# ServoShield_v2_2.net
KiCad netlist of a schematic drawn in EAGLE
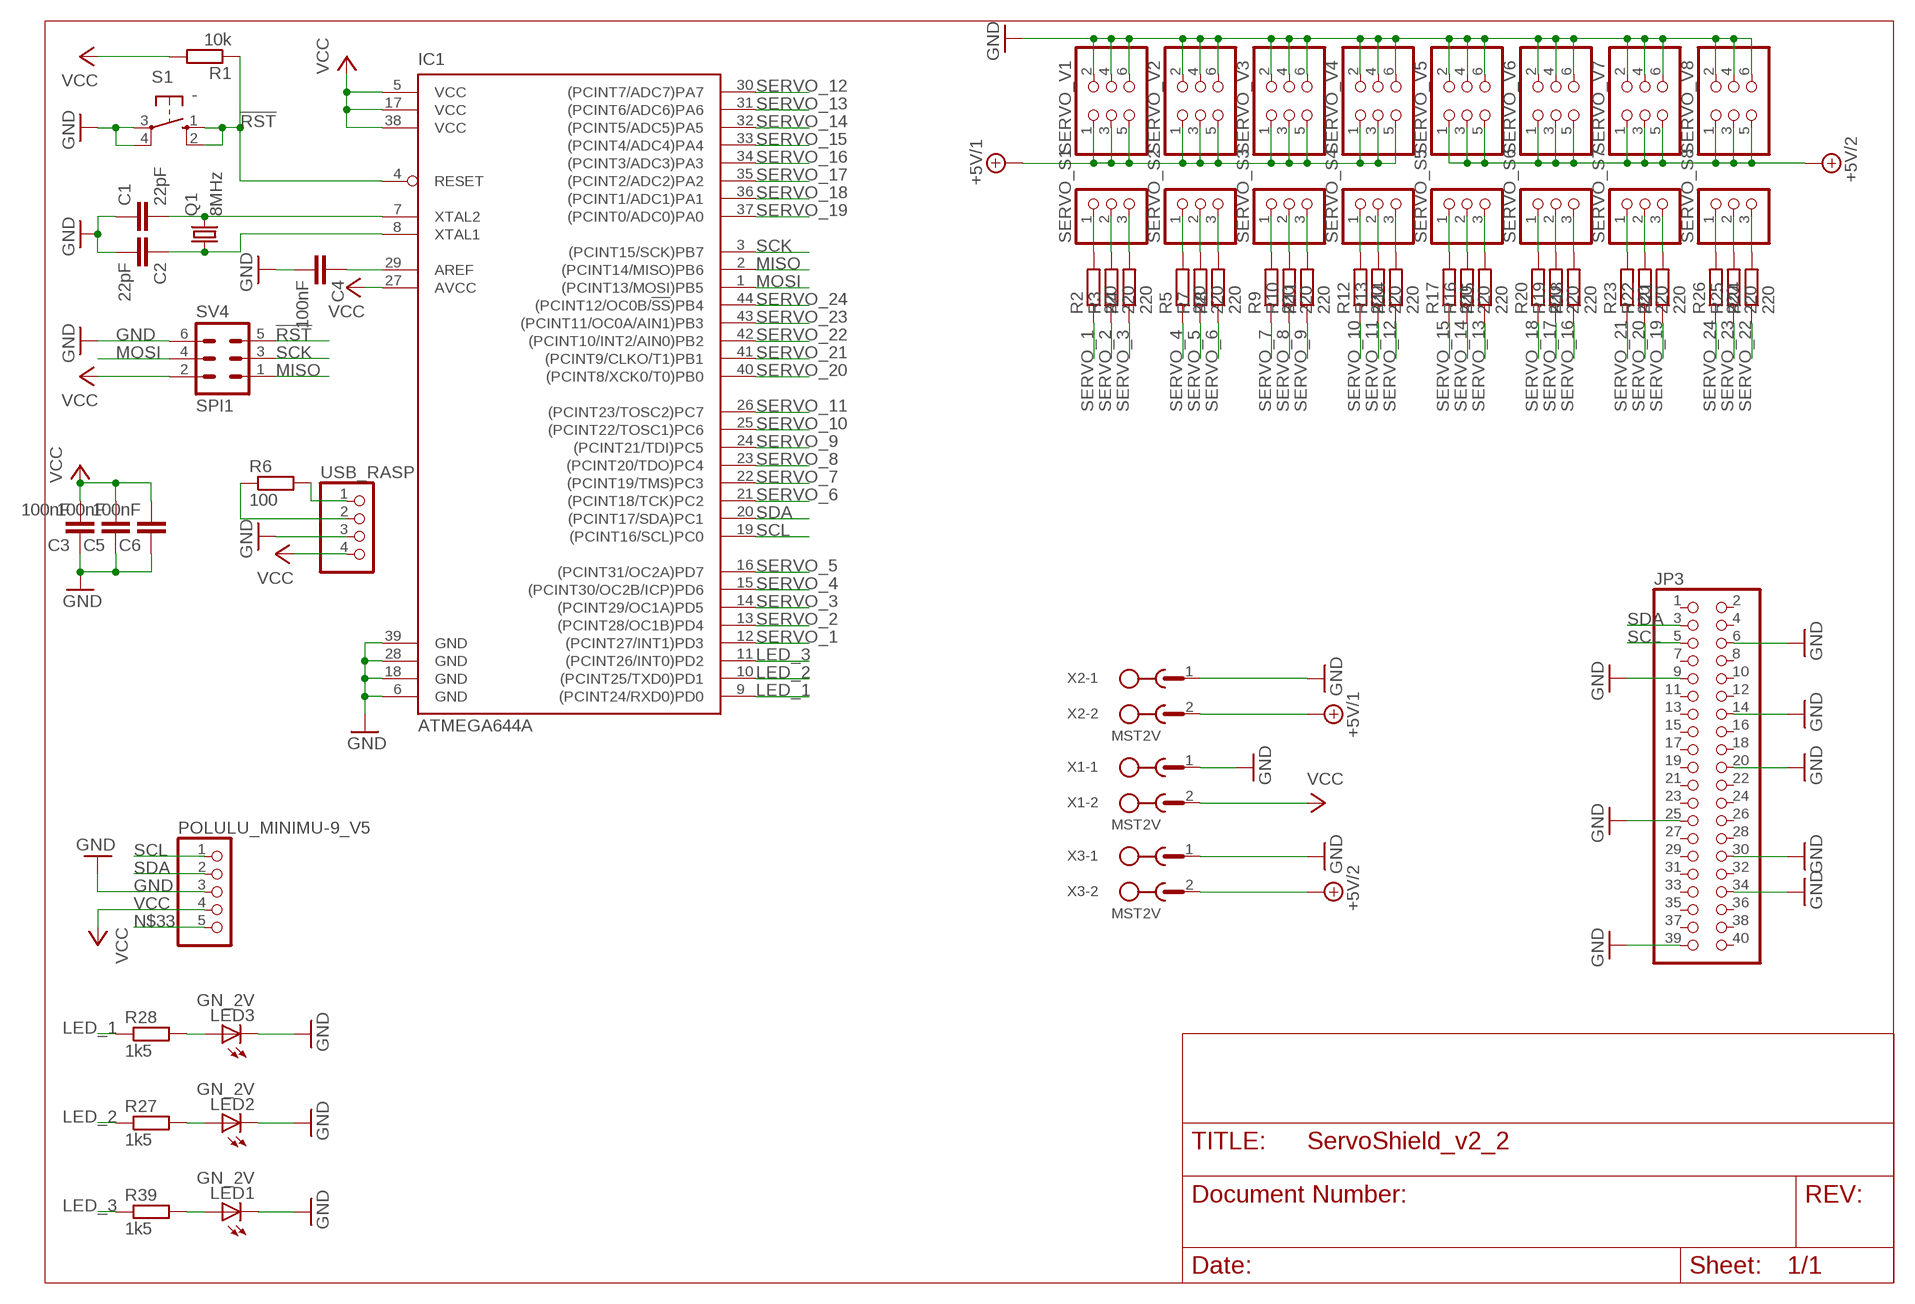
[diagram p0: schematic, sheet 1]

(export (version "E")
  (design (tool "Eeschema 10.0.6"))
  (components
    (comp (ref "C1")
      (value "22pF")
      (footprint "eagle-import:C0805")
      (libsource (lib "eagle-import") (part "C-EUC0805"))
    )
    (comp (ref "C2")
      (value "22pF")
      (footprint "eagle-import:C0805")
      (libsource (lib "eagle-import") (part "C-EUC0805"))
    )
    (comp (ref "C3")
      (value "100nF")
      (footprint "eagle-import:C0805")
      (libsource (lib "eagle-import") (part "resistor_C-EUC0805"))
    )
    (comp (ref "C4")
      (value "100nF")
      (footprint "eagle-import:C0805")
      (libsource (lib "eagle-import") (part "resistor_C-EUC0805"))
    )
    (comp (ref "C5")
      (value "100nF")
      (footprint "eagle-import:C0805")
      (libsource (lib "eagle-import") (part "resistor_C-EUC0805"))
    )
    (comp (ref "C6")
      (value "100nF")
      (footprint "eagle-import:C0805")
      (libsource (lib "eagle-import") (part "resistor_C-EUC0805"))
    )
    (comp (ref "IC1")
      (value "ATMEGA644A")
      (footprint "eagle-import:TQFP44")
      (fields (field (name "MPN") "ATMEGA644PV-10AU"))
      (libsource (lib "eagle-import") (part "ATMEGA644A"))
    )
    (comp (ref "JP3")
      (value "PINHD-2X20")
      (footprint "eagle-import:2X20")
      (libsource (lib "eagle-import") (part "PINHD-2X20"))
    )
    (comp (ref "LED1")
      (value "GN_2V")
      (footprint "eagle-import:LED3MM")
      (libsource (lib "eagle-import") (part "LED3MM"))
    )
    (comp (ref "LED2")
      (value "GN_2V")
      (footprint "eagle-import:LED3MM")
      (libsource (lib "eagle-import") (part "LED3MM"))
    )
    (comp (ref "LED3")
      (value "GN_2V")
      (footprint "eagle-import:LED3MM")
      (libsource (lib "eagle-import") (part "LED3MM"))
    )
    (comp (ref "POLULU_MINIMU-9_V5")
      (value "PINHD-1X5")
      (footprint "eagle-import:1X05")
      (libsource (lib "eagle-import") (part "PINHD-1X5"))
    )
    (comp (ref "Q1")
      (value "8MHz")
      (footprint "eagle-import:CTS406")
      (libsource (lib "eagle-import") (part "CRYSTALCTS406"))
    )
    (comp (ref "R1")
      (value "10k")
      (footprint "eagle-import:R0805")
      (libsource (lib "eagle-import") (part "resistor_R-EU_R0805"))
    )
    (comp (ref "R2")
      (value "220")
      (footprint "eagle-import:R0805")
      (libsource (lib "eagle-import") (part "resistor_R-EU_R0805"))
    )
    (comp (ref "R3")
      (value "220")
      (footprint "eagle-import:R0805")
      (libsource (lib "eagle-import") (part "resistor_R-EU_R0805"))
    )
    (comp (ref "R4")
      (value "220")
      (footprint "eagle-import:R0805")
      (libsource (lib "eagle-import") (part "resistor_R-EU_R0805"))
    )
    (comp (ref "R5")
      (value "220")
      (footprint "eagle-import:R0805")
      (libsource (lib "eagle-import") (part "resistor_R-EU_R0805"))
    )
    (comp (ref "R6")
      (value "100")
      (footprint "eagle-import:R0805")
      (libsource (lib "eagle-import") (part "R-EU_R0805"))
    )
    (comp (ref "R7")
      (value "220")
      (footprint "eagle-import:R0805")
      (libsource (lib "eagle-import") (part "resistor_R-EU_R0805"))
    )
    (comp (ref "R8")
      (value "220")
      (footprint "eagle-import:R0805")
      (libsource (lib "eagle-import") (part "resistor_R-EU_R0805"))
    )
    (comp (ref "R9")
      (value "220")
      (footprint "eagle-import:R0805")
      (libsource (lib "eagle-import") (part "resistor_R-EU_R0805"))
    )
    (comp (ref "R10")
      (value "220")
      (footprint "eagle-import:R0805")
      (libsource (lib "eagle-import") (part "resistor_R-EU_R0805"))
    )
    (comp (ref "R11")
      (value "220")
      (footprint "eagle-import:R0805")
      (libsource (lib "eagle-import") (part "resistor_R-EU_R0805"))
    )
    (comp (ref "R12")
      (value "220")
      (footprint "eagle-import:R0805")
      (libsource (lib "eagle-import") (part "resistor_R-EU_R0805"))
    )
    (comp (ref "R13")
      (value "220")
      (footprint "eagle-import:R0805")
      (libsource (lib "eagle-import") (part "resistor_R-EU_R0805"))
    )
    (comp (ref "R14")
      (value "220")
      (footprint "eagle-import:R0805")
      (libsource (lib "eagle-import") (part "resistor_R-EU_R0805"))
    )
    (comp (ref "R15")
      (value "220")
      (footprint "eagle-import:R0805")
      (libsource (lib "eagle-import") (part "resistor_R-EU_R0805"))
    )
    (comp (ref "R16")
      (value "220")
      (footprint "eagle-import:R0805")
      (libsource (lib "eagle-import") (part "resistor_R-EU_R0805"))
    )
    (comp (ref "R17")
      (value "220")
      (footprint "eagle-import:R0805")
      (libsource (lib "eagle-import") (part "resistor_R-EU_R0805"))
    )
    (comp (ref "R18")
      (value "220")
      (footprint "eagle-import:R0805")
      (libsource (lib "eagle-import") (part "resistor_R-EU_R0805"))
    )
    (comp (ref "R19")
      (value "220")
      (footprint "eagle-import:R0805")
      (libsource (lib "eagle-import") (part "resistor_R-EU_R0805"))
    )
    (comp (ref "R20")
      (value "220")
      (footprint "eagle-import:R0805")
      (libsource (lib "eagle-import") (part "resistor_R-EU_R0805"))
    )
    (comp (ref "R21")
      (value "220")
      (footprint "eagle-import:R0805")
      (libsource (lib "eagle-import") (part "resistor_R-EU_R0805"))
    )
    (comp (ref "R22")
      (value "220")
      (footprint "eagle-import:R0805")
      (libsource (lib "eagle-import") (part "resistor_R-EU_R0805"))
    )
    (comp (ref "R23")
      (value "220")
      (footprint "eagle-import:R0805")
      (libsource (lib "eagle-import") (part "resistor_R-EU_R0805"))
    )
    (comp (ref "R24")
      (value "220")
      (footprint "eagle-import:R0805")
      (libsource (lib "eagle-import") (part "resistor_R-EU_R0805"))
    )
    (comp (ref "R25")
      (value "220")
      (footprint "eagle-import:R0805")
      (libsource (lib "eagle-import") (part "resistor_R-EU_R0805"))
    )
    (comp (ref "R26")
      (value "220")
      (footprint "eagle-import:R0805")
      (libsource (lib "eagle-import") (part "resistor_R-EU_R0805"))
    )
    (comp (ref "R27")
      (value "1k5")
      (footprint "eagle-import:R0805")
      (libsource (lib "eagle-import") (part "R-EU_R0805"))
    )
    (comp (ref "R28")
      (value "1k5")
      (footprint "eagle-import:R0805")
      (libsource (lib "eagle-import") (part "R-EU_R0805"))
    )
    (comp (ref "R39")
      (value "1k5")
      (footprint "eagle-import:R0805")
      (libsource (lib "eagle-import") (part "R-EU_R0805"))
    )
    (comp (ref "S1")
      (value "-")
      (footprint "eagle-import:B3F-10XX")
      (fields (field (name "MPN") "B3F-1000"))
      (libsource (lib "eagle-import") (part "10-XX"))
    )
    (comp (ref "SERVO_S1")
      (value "PINHD-1X3")
      (footprint "eagle-import:1X03")
      (libsource (lib "eagle-import") (part "PINHD-1X3"))
    )
    (comp (ref "SERVO_S2")
      (value "PINHD-1X3")
      (footprint "eagle-import:1X03")
      (libsource (lib "eagle-import") (part "PINHD-1X3"))
    )
    (comp (ref "SERVO_S3")
      (value "PINHD-1X3")
      (footprint "eagle-import:1X03")
      (libsource (lib "eagle-import") (part "PINHD-1X3"))
    )
    (comp (ref "SERVO_S4")
      (value "PINHD-1X3")
      (footprint "eagle-import:1X03")
      (libsource (lib "eagle-import") (part "PINHD-1X3"))
    )
    (comp (ref "SERVO_S5")
      (value "PINHD-1X3")
      (footprint "eagle-import:1X03")
      (libsource (lib "eagle-import") (part "PINHD-1X3"))
    )
    (comp (ref "SERVO_S6")
      (value "PINHD-1X3")
      (footprint "eagle-import:1X03")
      (libsource (lib "eagle-import") (part "PINHD-1X3"))
    )
    (comp (ref "SERVO_S7")
      (value "PINHD-1X3")
      (footprint "eagle-import:1X03")
      (libsource (lib "eagle-import") (part "PINHD-1X3"))
    )
    (comp (ref "SERVO_S8")
      (value "PINHD-1X3")
      (footprint "eagle-import:1X03")
      (libsource (lib "eagle-import") (part "PINHD-1X3"))
    )
    (comp (ref "SERVO_V1")
      (value "PINHD-2X3")
      (footprint "eagle-import:2X03")
      (libsource (lib "eagle-import") (part "PINHD-2X3"))
    )
    (comp (ref "SERVO_V2")
      (value "PINHD-2X3")
      (footprint "eagle-import:2X03")
      (libsource (lib "eagle-import") (part "PINHD-2X3"))
    )
    (comp (ref "SERVO_V3")
      (value "PINHD-2X3")
      (footprint "eagle-import:2X03")
      (libsource (lib "eagle-import") (part "PINHD-2X3"))
    )
    (comp (ref "SERVO_V4")
      (value "PINHD-2X3")
      (footprint "eagle-import:2X03")
      (libsource (lib "eagle-import") (part "PINHD-2X3"))
    )
    (comp (ref "SERVO_V5")
      (value "PINHD-2X3")
      (footprint "eagle-import:2X03")
      (libsource (lib "eagle-import") (part "PINHD-2X3"))
    )
    (comp (ref "SERVO_V6")
      (value "PINHD-2X3")
      (footprint "eagle-import:2X03")
      (libsource (lib "eagle-import") (part "PINHD-2X3"))
    )
    (comp (ref "SERVO_V7")
      (value "PINHD-2X3")
      (footprint "eagle-import:2X03")
      (libsource (lib "eagle-import") (part "PINHD-2X3"))
    )
    (comp (ref "SERVO_V8")
      (value "PINHD-2X3")
      (footprint "eagle-import:2X03")
      (libsource (lib "eagle-import") (part "PINHD-2X3"))
    )
    (comp (ref "SV4")
      (value "SPI1")
      (footprint "eagle-import:ML6")
      (libsource (lib "eagle-import") (part "ML6"))
    )
    (comp (ref "USB_RASP")
      (value "PINHD-1X4")
      (footprint "eagle-import:1X04")
      (libsource (lib "eagle-import") (part "PINHD-1X4"))
    )
    (comp (ref "X1")
      (value "MST2V")
      (footprint "eagle-import:MSTBV2")
      (libsource (lib "eagle-import") (part "MST2V"))
    )
    (comp (ref "X2")
      (value "MST2V")
      (footprint "eagle-import:MSTBV2")
      (libsource (lib "eagle-import") (part "MST2V"))
    )
    (comp (ref "X3")
      (value "MST2V")
      (footprint "eagle-import:MSTBV2")
      (libsource (lib "eagle-import") (part "MST2V"))
    )
  )
  (nets
    (net (code "1") (name "+5V{slash}1") (class "Default")
      (node (ref "SERVO_V1") (pin "1") (pinfunction "1_1") (pintype "passive"))
      (node (ref "SERVO_V1") (pin "3") (pinfunction "3_3") (pintype "passive"))
      (node (ref "SERVO_V1") (pin "5") (pinfunction "5_5") (pintype "passive"))
      (node (ref "SERVO_V2") (pin "1") (pinfunction "1_1") (pintype "passive"))
      (node (ref "SERVO_V2") (pin "3") (pinfunction "3_3") (pintype "passive"))
      (node (ref "SERVO_V2") (pin "5") (pinfunction "5_5") (pintype "passive"))
      (node (ref "SERVO_V3") (pin "1") (pinfunction "1_1") (pintype "passive"))
      (node (ref "SERVO_V3") (pin "3") (pinfunction "3_3") (pintype "passive"))
      (node (ref "SERVO_V3") (pin "5") (pinfunction "5_5") (pintype "passive"))
      (node (ref "SERVO_V4") (pin "1") (pinfunction "1_1") (pintype "passive"))
      (node (ref "SERVO_V4") (pin "3") (pinfunction "3_3") (pintype "passive"))
      (node (ref "SERVO_V4") (pin "5") (pinfunction "5_5") (pintype "passive"))
      (node (ref "X2") (pin "2") (pinfunction "1_2") (pintype "passive"))
    )
    (net (code "2") (name "+5V{slash}2") (class "Default")
      (node (ref "SERVO_V5") (pin "1") (pinfunction "1_1") (pintype "passive"))
      (node (ref "SERVO_V5") (pin "3") (pinfunction "3_3") (pintype "passive"))
      (node (ref "SERVO_V5") (pin "5") (pinfunction "5_5") (pintype "passive"))
      (node (ref "SERVO_V6") (pin "1") (pinfunction "1_1") (pintype "passive"))
      (node (ref "SERVO_V6") (pin "3") (pinfunction "3_3") (pintype "passive"))
      (node (ref "SERVO_V6") (pin "5") (pinfunction "5_5") (pintype "passive"))
      (node (ref "SERVO_V7") (pin "1") (pinfunction "1_1") (pintype "passive"))
      (node (ref "SERVO_V7") (pin "3") (pinfunction "3_3") (pintype "passive"))
      (node (ref "SERVO_V7") (pin "5") (pinfunction "5_5") (pintype "passive"))
      (node (ref "SERVO_V8") (pin "1") (pinfunction "1_1") (pintype "passive"))
      (node (ref "SERVO_V8") (pin "3") (pinfunction "3_3") (pintype "passive"))
      (node (ref "SERVO_V8") (pin "5") (pinfunction "5_5") (pintype "passive"))
      (node (ref "X3") (pin "2") (pinfunction "1_2") (pintype "passive"))
    )
    (net (code "3") (name "/LED_1") (class "Default")
      (node (ref "IC1") (pin "9") (pinfunction "(PCINT24/RXD0)PD0_9") (pintype "bidirectional"))
      (node (ref "R28") (pin "1") (pinfunction "1_1") (pintype "passive"))
    )
    (net (code "4") (name "/LED_2") (class "Default")
      (node (ref "IC1") (pin "10") (pinfunction "(PCINT25/TXD0)PD1_10") (pintype "bidirectional"))
      (node (ref "R27") (pin "1") (pinfunction "1_1") (pintype "passive"))
    )
    (net (code "5") (name "/LED_3") (class "Default")
      (node (ref "IC1") (pin "11") (pinfunction "(PCINT26/INT0)PD2_11") (pintype "bidirectional"))
      (node (ref "R39") (pin "1") (pinfunction "1_1") (pintype "passive"))
    )
    (net (code "6") (name "/MISO") (class "Default")
      (node (ref "IC1") (pin "2") (pinfunction "(PCINT14/MISO)PB6_2") (pintype "bidirectional"))
      (node (ref "SV4") (pin "1") (pinfunction "1_1") (pintype "passive"))
    )
    (net (code "7") (name "/MOSI") (class "Default")
      (node (ref "IC1") (pin "1") (pinfunction "(PCINT13/MOSI)PB5_1") (pintype "bidirectional"))
      (node (ref "SV4") (pin "4") (pinfunction "4_4") (pintype "passive"))
    )
    (net (code "8") (name "/N$33") (class "Default")
      (node (ref "POLULU_MINIMU-9_V5") (pin "5") (pinfunction "5_5") (pintype "passive"))
    )
    (net (code "9") (name "/SCK") (class "Default")
      (node (ref "IC1") (pin "3") (pinfunction "(PCINT15/SCK)PB7_3") (pintype "bidirectional"))
      (node (ref "SV4") (pin "3") (pinfunction "3_3") (pintype "passive"))
    )
    (net (code "10") (name "/SCL") (class "Default")
      (node (ref "IC1") (pin "19") (pinfunction "(PCINT16/SCL)PC0_19") (pintype "output"))
      (node (ref "JP3") (pin "5") (pinfunction "5_5") (pintype "passive"))
      (node (ref "POLULU_MINIMU-9_V5") (pin "1") (pinfunction "1_1") (pintype "passive"))
    )
    (net (code "11") (name "/SDA") (class "Default")
      (node (ref "IC1") (pin "20") (pinfunction "(PCINT17/SDA)PC1_20") (pintype "output"))
      (node (ref "JP3") (pin "3") (pinfunction "3_3") (pintype "passive"))
      (node (ref "POLULU_MINIMU-9_V5") (pin "2") (pinfunction "2_2") (pintype "passive"))
    )
    (net (code "12") (name "/SERVO_1") (class "Default")
      (node (ref "IC1") (pin "12") (pinfunction "(PCINT27/INT1)PD3_12") (pintype "bidirectional"))
      (node (ref "R2") (pin "1") (pinfunction "1_1") (pintype "passive"))
    )
    (net (code "13") (name "/SERVO_2") (class "Default")
      (node (ref "IC1") (pin "13") (pinfunction "(PCINT28/OC1B)PD4_13") (pintype "bidirectional"))
      (node (ref "R3") (pin "1") (pinfunction "1_1") (pintype "passive"))
    )
    (net (code "14") (name "/SERVO_3") (class "Default")
      (node (ref "IC1") (pin "14") (pinfunction "(PCINT29/OC1A)PD5_14") (pintype "bidirectional"))
      (node (ref "R4") (pin "1") (pinfunction "1_1") (pintype "passive"))
    )
    (net (code "15") (name "/SERVO_4") (class "Default")
      (node (ref "IC1") (pin "15") (pinfunction "(PCINT30/OC2B/ICP)PD6_15") (pintype "bidirectional"))
      (node (ref "R5") (pin "1") (pinfunction "1_1") (pintype "passive"))
    )
    (net (code "16") (name "/SERVO_5") (class "Default")
      (node (ref "IC1") (pin "16") (pinfunction "(PCINT31/OC2A)PD7_16") (pintype "bidirectional"))
      (node (ref "R7") (pin "1") (pinfunction "1_1") (pintype "passive"))
    )
    (net (code "17") (name "/SERVO_6") (class "Default")
      (node (ref "IC1") (pin "21") (pinfunction "(PCINT18/TCK)PC2_21") (pintype "output"))
      (node (ref "R8") (pin "1") (pinfunction "1_1") (pintype "passive"))
    )
    (net (code "18") (name "/SERVO_7") (class "Default")
      (node (ref "IC1") (pin "22") (pinfunction "(PCINT19/TMS)PC3_22") (pintype "output"))
      (node (ref "R9") (pin "1") (pinfunction "1_1") (pintype "passive"))
    )
    (net (code "19") (name "/SERVO_8") (class "Default")
      (node (ref "IC1") (pin "23") (pinfunction "(PCINT20/TDO)PC4_23") (pintype "output"))
      (node (ref "R10") (pin "1") (pinfunction "1_1") (pintype "passive"))
    )
    (net (code "20") (name "/SERVO_9") (class "Default")
      (node (ref "IC1") (pin "24") (pinfunction "(PCINT21/TDI)PC5_24") (pintype "output"))
      (node (ref "R11") (pin "1") (pinfunction "1_1") (pintype "passive"))
    )
    (net (code "21") (name "/SERVO_10") (class "Default")
      (node (ref "IC1") (pin "25") (pinfunction "(PCINT22/TOSC1)PC6_25") (pintype "output"))
      (node (ref "R12") (pin "1") (pinfunction "1_1") (pintype "passive"))
    )
    (net (code "22") (name "/SERVO_11") (class "Default")
      (node (ref "IC1") (pin "26") (pinfunction "(PCINT23/TOSC2)PC7_26") (pintype "output"))
      (node (ref "R13") (pin "1") (pinfunction "1_1") (pintype "passive"))
    )
    (net (code "23") (name "/SERVO_12") (class "Default")
      (node (ref "IC1") (pin "30") (pinfunction "(PCINT7/ADC7)PA7_30") (pintype "bidirectional"))
      (node (ref "R14") (pin "1") (pinfunction "1_1") (pintype "passive"))
    )
    (net (code "24") (name "/SERVO_13") (class "Default")
      (node (ref "IC1") (pin "31") (pinfunction "(PCINT6/ADC6)PA6_31") (pintype "bidirectional"))
      (node (ref "R15") (pin "1") (pinfunction "1_1") (pintype "passive"))
    )
    (net (code "25") (name "/SERVO_14") (class "Default")
      (node (ref "IC1") (pin "32") (pinfunction "(PCINT5/ADC5)PA5_32") (pintype "bidirectional"))
      (node (ref "R16") (pin "1") (pinfunction "1_1") (pintype "passive"))
    )
    (net (code "26") (name "/SERVO_15") (class "Default")
      (node (ref "IC1") (pin "33") (pinfunction "(PCINT4/ADC4)PA4_33") (pintype "bidirectional"))
      (node (ref "R17") (pin "1") (pinfunction "1_1") (pintype "passive"))
    )
    (net (code "27") (name "/SERVO_16") (class "Default")
      (node (ref "IC1") (pin "34") (pinfunction "(PCINT3/ADC3)PA3_34") (pintype "bidirectional"))
      (node (ref "R18") (pin "1") (pinfunction "1_1") (pintype "passive"))
    )
    (net (code "28") (name "/SERVO_17") (class "Default")
      (node (ref "IC1") (pin "35") (pinfunction "(PCINT2/ADC2)PA2_35") (pintype "bidirectional"))
      (node (ref "R19") (pin "1") (pinfunction "1_1") (pintype "passive"))
    )
    (net (code "29") (name "/SERVO_18") (class "Default")
      (node (ref "IC1") (pin "36") (pinfunction "(PCINT1/ADC1)PA1_36") (pintype "bidirectional"))
      (node (ref "R20") (pin "1") (pinfunction "1_1") (pintype "passive"))
    )
    (net (code "30") (name "/SERVO_19") (class "Default")
      (node (ref "IC1") (pin "37") (pinfunction "(PCINT0/ADC0)PA0_37") (pintype "bidirectional"))
      (node (ref "R21") (pin "1") (pinfunction "1_1") (pintype "passive"))
    )
    (net (code "31") (name "/SERVO_20") (class "Default")
      (node (ref "IC1") (pin "40") (pinfunction "(PCINT8/XCK0/T0)PB0_40") (pintype "bidirectional"))
      (node (ref "R22") (pin "1") (pinfunction "1_1") (pintype "passive"))
    )
    (net (code "32") (name "/SERVO_21") (class "Default")
      (node (ref "IC1") (pin "41") (pinfunction "(PCINT9/CLKO/T1)PB1_41") (pintype "bidirectional"))
      (node (ref "R23") (pin "1") (pinfunction "1_1") (pintype "passive"))
    )
    (net (code "33") (name "/SERVO_22") (class "Default")
      (node (ref "IC1") (pin "42") (pinfunction "(PCINT10/INT2/AIN0)PB2_42") (pintype "bidirectional"))
      (node (ref "R24") (pin "1") (pinfunction "1_1") (pintype "passive"))
    )
    (net (code "34") (name "/SERVO_23") (class "Default")
      (node (ref "IC1") (pin "43") (pinfunction "(PCINT11/OC0A/AIN1)PB3_43") (pintype "bidirectional"))
      (node (ref "R25") (pin "1") (pinfunction "1_1") (pintype "passive"))
    )
    (net (code "35") (name "/SERVO_24") (class "Default")
      (node (ref "IC1") (pin "44") (pinfunction "(PCINT12/OC0B/~{SS})PB4_44") (pintype "bidirectional"))
      (node (ref "R26") (pin "1") (pinfunction "1_1") (pintype "passive"))
    )
    (net (code "36") (name "/~{RST}") (class "Default")
      (node (ref "IC1") (pin "4") (pinfunction "RESET_4") (pintype "input"))
      (node (ref "R1") (pin "1") (pinfunction "1_1") (pintype "passive"))
      (node (ref "S1") (pin "1") (pinfunction "S_1") (pintype "passive"))
      (node (ref "S1") (pin "2") (pinfunction "S1_2") (pintype "passive"))
      (node (ref "SV4") (pin "5") (pinfunction "5_5") (pintype "passive"))
    )
    (net (code "37") (name "GND") (class "Default")
      (node (ref "C1") (pin "1") (pinfunction "1_1") (pintype "passive"))
      (node (ref "C2") (pin "2") (pinfunction "2_2") (pintype "passive"))
      (node (ref "C3") (pin "1") (pinfunction "1_1") (pintype "passive"))
      (node (ref "C4") (pin "2") (pinfunction "2_2") (pintype "passive"))
      (node (ref "C5") (pin "1") (pinfunction "1_1") (pintype "passive"))
      (node (ref "C6") (pin "1") (pinfunction "1_1") (pintype "passive"))
      (node (ref "IC1") (pin "18") (pinfunction "GND_18") (pintype "power_in"))
      (node (ref "IC1") (pin "28") (pinfunction "GND_28") (pintype "power_in"))
      (node (ref "IC1") (pin "39") (pinfunction "GND_39") (pintype "power_in"))
      (node (ref "IC1") (pin "6") (pinfunction "GND_6") (pintype "power_in"))
      (node (ref "JP3") (pin "14") (pinfunction "14_14") (pintype "passive"))
      (node (ref "JP3") (pin "20") (pinfunction "20_20") (pintype "passive"))
      (node (ref "JP3") (pin "25") (pinfunction "25_25") (pintype "passive"))
      (node (ref "JP3") (pin "30") (pinfunction "30_30") (pintype "passive"))
      (node (ref "JP3") (pin "34") (pinfunction "34_34") (pintype "passive"))
      (node (ref "JP3") (pin "39") (pinfunction "39_39") (pintype "passive"))
      (node (ref "JP3") (pin "6") (pinfunction "6_6") (pintype "passive"))
      (node (ref "JP3") (pin "9") (pinfunction "9_9") (pintype "passive"))
      (node (ref "LED1") (pin "K") (pinfunction "C_K") (pintype "passive"))
      (node (ref "LED2") (pin "K") (pinfunction "C_K") (pintype "passive"))
      (node (ref "LED3") (pin "K") (pinfunction "C_K") (pintype "passive"))
      (node (ref "POLULU_MINIMU-9_V5") (pin "3") (pinfunction "3_3") (pintype "passive"))
      (node (ref "S1") (pin "3") (pinfunction "P_3") (pintype "passive"))
      (node (ref "S1") (pin "4") (pinfunction "P1_4") (pintype "passive"))
      (node (ref "SERVO_V1") (pin "2") (pinfunction "2_2") (pintype "passive"))
      (node (ref "SERVO_V1") (pin "4") (pinfunction "4_4") (pintype "passive"))
      (node (ref "SERVO_V1") (pin "6") (pinfunction "6_6") (pintype "passive"))
      (node (ref "SERVO_V2") (pin "2") (pinfunction "2_2") (pintype "passive"))
      (node (ref "SERVO_V2") (pin "4") (pinfunction "4_4") (pintype "passive"))
      (node (ref "SERVO_V2") (pin "6") (pinfunction "6_6") (pintype "passive"))
      (node (ref "SERVO_V3") (pin "2") (pinfunction "2_2") (pintype "passive"))
      (node (ref "SERVO_V3") (pin "4") (pinfunction "4_4") (pintype "passive"))
      (node (ref "SERVO_V3") (pin "6") (pinfunction "6_6") (pintype "passive"))
      (node (ref "SERVO_V4") (pin "2") (pinfunction "2_2") (pintype "passive"))
      (node (ref "SERVO_V4") (pin "4") (pinfunction "4_4") (pintype "passive"))
      (node (ref "SERVO_V4") (pin "6") (pinfunction "6_6") (pintype "passive"))
      (node (ref "SERVO_V5") (pin "2") (pinfunction "2_2") (pintype "passive"))
      (node (ref "SERVO_V5") (pin "4") (pinfunction "4_4") (pintype "passive"))
      (node (ref "SERVO_V5") (pin "6") (pinfunction "6_6") (pintype "passive"))
      (node (ref "SERVO_V6") (pin "2") (pinfunction "2_2") (pintype "passive"))
      (node (ref "SERVO_V6") (pin "4") (pinfunction "4_4") (pintype "passive"))
      (node (ref "SERVO_V6") (pin "6") (pinfunction "6_6") (pintype "passive"))
      (node (ref "SERVO_V7") (pin "2") (pinfunction "2_2") (pintype "passive"))
      (node (ref "SERVO_V7") (pin "4") (pinfunction "4_4") (pintype "passive"))
      (node (ref "SERVO_V7") (pin "6") (pinfunction "6_6") (pintype "passive"))
      (node (ref "SERVO_V8") (pin "2") (pinfunction "2_2") (pintype "passive"))
      (node (ref "SERVO_V8") (pin "4") (pinfunction "4_4") (pintype "passive"))
      (node (ref "SERVO_V8") (pin "6") (pinfunction "6_6") (pintype "passive"))
      (node (ref "SV4") (pin "6") (pinfunction "6_6") (pintype "passive"))
      (node (ref "USB_RASP") (pin "3") (pinfunction "3_3") (pintype "passive"))
      (node (ref "X1") (pin "1") (pinfunction "1_1") (pintype "passive"))
      (node (ref "X2") (pin "1") (pinfunction "1_1") (pintype "passive"))
      (node (ref "X3") (pin "1") (pinfunction "1_1") (pintype "passive"))
    )
    (net (code "38") (name "Net-(IC1-AREF)") (class "Default")
      (node (ref "C4") (pin "1") (pinfunction "1_1") (pintype "passive"))
      (node (ref "IC1") (pin "29") (pinfunction "AREF_29") (pintype "passive"))
    )
    (net (code "39") (name "Net-(IC1-XTAL1)") (class "Default")
      (node (ref "C2") (pin "1") (pinfunction "1_1") (pintype "passive"))
      (node (ref "IC1") (pin "8") (pinfunction "XTAL1_8") (pintype "bidirectional"))
      (node (ref "Q1") (pin "1") (pinfunction "1_1") (pintype "passive"))
    )
    (net (code "40") (name "Net-(IC1-XTAL2)") (class "Default")
      (node (ref "C1") (pin "2") (pinfunction "2_2") (pintype "passive"))
      (node (ref "IC1") (pin "7") (pinfunction "XTAL2_7") (pintype "bidirectional"))
      (node (ref "Q1") (pin "3") (pinfunction "2_3") (pintype "passive"))
    )
    (net (code "41") (name "Net-(LED1-PadA)") (class "Default")
      (node (ref "LED1") (pin "A") (pinfunction "A_A") (pintype "passive"))
      (node (ref "R39") (pin "2") (pinfunction "2_2") (pintype "passive"))
    )
    (net (code "42") (name "Net-(LED2-PadA)") (class "Default")
      (node (ref "LED2") (pin "A") (pinfunction "A_A") (pintype "passive"))
      (node (ref "R27") (pin "2") (pinfunction "2_2") (pintype "passive"))
    )
    (net (code "43") (name "Net-(LED3-PadA)") (class "Default")
      (node (ref "LED3") (pin "A") (pinfunction "A_A") (pintype "passive"))
      (node (ref "R28") (pin "2") (pinfunction "2_2") (pintype "passive"))
    )
    (net (code "44") (name "Net-(R2-Pad2)") (class "Default")
      (node (ref "R2") (pin "2") (pinfunction "2_2") (pintype "passive"))
      (node (ref "SERVO_S1") (pin "1") (pinfunction "1_1") (pintype "passive"))
    )
    (net (code "45") (name "Net-(R3-Pad2)") (class "Default")
      (node (ref "R3") (pin "2") (pinfunction "2_2") (pintype "passive"))
      (node (ref "SERVO_S1") (pin "2") (pinfunction "2_2") (pintype "passive"))
    )
    (net (code "46") (name "Net-(R4-Pad2)") (class "Default")
      (node (ref "R4") (pin "2") (pinfunction "2_2") (pintype "passive"))
      (node (ref "SERVO_S1") (pin "3") (pinfunction "3_3") (pintype "passive"))
    )
    (net (code "47") (name "Net-(R5-Pad2)") (class "Default")
      (node (ref "R5") (pin "2") (pinfunction "2_2") (pintype "passive"))
      (node (ref "SERVO_S2") (pin "1") (pinfunction "1_1") (pintype "passive"))
    )
    (net (code "48") (name "Net-(R6-Pad1)") (class "Default")
      (node (ref "R6") (pin "1") (pinfunction "1_1") (pintype "passive"))
      (node (ref "USB_RASP") (pin "2") (pinfunction "2_2") (pintype "passive"))
    )
    (net (code "49") (name "Net-(R6-Pad2)") (class "Default")
      (node (ref "R6") (pin "2") (pinfunction "2_2") (pintype "passive"))
      (node (ref "USB_RASP") (pin "1") (pinfunction "1_1") (pintype "passive"))
    )
    (net (code "50") (name "Net-(R7-Pad2)") (class "Default")
      (node (ref "R7") (pin "2") (pinfunction "2_2") (pintype "passive"))
      (node (ref "SERVO_S2") (pin "2") (pinfunction "2_2") (pintype "passive"))
    )
    (net (code "51") (name "Net-(R8-Pad2)") (class "Default")
      (node (ref "R8") (pin "2") (pinfunction "2_2") (pintype "passive"))
      (node (ref "SERVO_S2") (pin "3") (pinfunction "3_3") (pintype "passive"))
    )
    (net (code "52") (name "Net-(R9-Pad2)") (class "Default")
      (node (ref "R9") (pin "2") (pinfunction "2_2") (pintype "passive"))
      (node (ref "SERVO_S3") (pin "1") (pinfunction "1_1") (pintype "passive"))
    )
    (net (code "53") (name "Net-(R10-Pad2)") (class "Default")
      (node (ref "R10") (pin "2") (pinfunction "2_2") (pintype "passive"))
      (node (ref "SERVO_S3") (pin "2") (pinfunction "2_2") (pintype "passive"))
    )
    (net (code "54") (name "Net-(R11-Pad2)") (class "Default")
      (node (ref "R11") (pin "2") (pinfunction "2_2") (pintype "passive"))
      (node (ref "SERVO_S3") (pin "3") (pinfunction "3_3") (pintype "passive"))
    )
    (net (code "55") (name "Net-(R12-Pad2)") (class "Default")
      (node (ref "R12") (pin "2") (pinfunction "2_2") (pintype "passive"))
      (node (ref "SERVO_S4") (pin "1") (pinfunction "1_1") (pintype "passive"))
    )
    (net (code "56") (name "Net-(R13-Pad2)") (class "Default")
      (node (ref "R13") (pin "2") (pinfunction "2_2") (pintype "passive"))
      (node (ref "SERVO_S4") (pin "2") (pinfunction "2_2") (pintype "passive"))
    )
    (net (code "57") (name "Net-(R14-Pad2)") (class "Default")
      (node (ref "R14") (pin "2") (pinfunction "2_2") (pintype "passive"))
      (node (ref "SERVO_S4") (pin "3") (pinfunction "3_3") (pintype "passive"))
    )
    (net (code "58") (name "Net-(R15-Pad2)") (class "Default")
      (node (ref "R15") (pin "2") (pinfunction "2_2") (pintype "passive"))
      (node (ref "SERVO_S5") (pin "3") (pinfunction "3_3") (pintype "passive"))
    )
    (net (code "59") (name "Net-(R16-Pad2)") (class "Default")
      (node (ref "R16") (pin "2") (pinfunction "2_2") (pintype "passive"))
      (node (ref "SERVO_S5") (pin "2") (pinfunction "2_2") (pintype "passive"))
    )
    (net (code "60") (name "Net-(R17-Pad2)") (class "Default")
      (node (ref "R17") (pin "2") (pinfunction "2_2") (pintype "passive"))
      (node (ref "SERVO_S5") (pin "1") (pinfunction "1_1") (pintype "passive"))
    )
    (net (code "61") (name "Net-(R18-Pad2)") (class "Default")
      (node (ref "R18") (pin "2") (pinfunction "2_2") (pintype "passive"))
      (node (ref "SERVO_S6") (pin "3") (pinfunction "3_3") (pintype "passive"))
    )
    (net (code "62") (name "Net-(R19-Pad2)") (class "Default")
      (node (ref "R19") (pin "2") (pinfunction "2_2") (pintype "passive"))
      (node (ref "SERVO_S6") (pin "2") (pinfunction "2_2") (pintype "passive"))
    )
    (net (code "63") (name "Net-(R20-Pad2)") (class "Default")
      (node (ref "R20") (pin "2") (pinfunction "2_2") (pintype "passive"))
      (node (ref "SERVO_S6") (pin "1") (pinfunction "1_1") (pintype "passive"))
    )
    (net (code "64") (name "Net-(R21-Pad2)") (class "Default")
      (node (ref "R21") (pin "2") (pinfunction "2_2") (pintype "passive"))
      (node (ref "SERVO_S7") (pin "3") (pinfunction "3_3") (pintype "passive"))
    )
    (net (code "65") (name "Net-(R22-Pad2)") (class "Default")
      (node (ref "R22") (pin "2") (pinfunction "2_2") (pintype "passive"))
      (node (ref "SERVO_S7") (pin "2") (pinfunction "2_2") (pintype "passive"))
    )
    (net (code "66") (name "Net-(R23-Pad2)") (class "Default")
      (node (ref "R23") (pin "2") (pinfunction "2_2") (pintype "passive"))
      (node (ref "SERVO_S7") (pin "1") (pinfunction "1_1") (pintype "passive"))
    )
    (net (code "67") (name "Net-(R24-Pad2)") (class "Default")
      (node (ref "R24") (pin "2") (pinfunction "2_2") (pintype "passive"))
      (node (ref "SERVO_S8") (pin "3") (pinfunction "3_3") (pintype "passive"))
    )
    (net (code "68") (name "Net-(R25-Pad2)") (class "Default")
      (node (ref "R25") (pin "2") (pinfunction "2_2") (pintype "passive"))
      (node (ref "SERVO_S8") (pin "2") (pinfunction "2_2") (pintype "passive"))
    )
    (net (code "69") (name "Net-(R26-Pad2)") (class "Default")
      (node (ref "R26") (pin "2") (pinfunction "2_2") (pintype "passive"))
      (node (ref "SERVO_S8") (pin "1") (pinfunction "1_1") (pintype "passive"))
    )
    (net (code "70") (name "VCC") (class "Default")
      (node (ref "C3") (pin "2") (pinfunction "2_2") (pintype "passive"))
      (node (ref "C5") (pin "2") (pinfunction "2_2") (pintype "passive"))
      (node (ref "C6") (pin "2") (pinfunction "2_2") (pintype "passive"))
      (node (ref "IC1") (pin "17") (pinfunction "VCC_17") (pintype "power_in"))
      (node (ref "IC1") (pin "27") (pinfunction "AVCC_27") (pintype "power_in"))
      (node (ref "IC1") (pin "38") (pinfunction "VCC_38") (pintype "power_in"))
      (node (ref "IC1") (pin "5") (pinfunction "VCC_5") (pintype "power_in"))
      (node (ref "POLULU_MINIMU-9_V5") (pin "4") (pinfunction "4_4") (pintype "passive"))
      (node (ref "R1") (pin "2") (pinfunction "2_2") (pintype "passive"))
      (node (ref "SV4") (pin "2") (pinfunction "2_2") (pintype "passive"))
      (node (ref "USB_RASP") (pin "4") (pinfunction "4_4") (pintype "passive"))
      (node (ref "X1") (pin "2") (pinfunction "1_2") (pintype "passive"))
    )
    (net (code "71") (name "unconnected-(JP3-Pad1)") (class "Default")
      (node (ref "JP3") (pin "1") (pinfunction "1_1") (pintype "passive"))
    )
    (net (code "72") (name "unconnected-(JP3-Pad2)") (class "Default")
      (node (ref "JP3") (pin "2") (pinfunction "2_2") (pintype "passive"))
    )
    (net (code "73") (name "unconnected-(JP3-Pad4)") (class "Default")
      (node (ref "JP3") (pin "4") (pinfunction "4_4") (pintype "passive"))
    )
    (net (code "74") (name "unconnected-(JP3-Pad7)") (class "Default")
      (node (ref "JP3") (pin "7") (pinfunction "7_7") (pintype "passive"))
    )
    (net (code "75") (name "unconnected-(JP3-Pad8)") (class "Default")
      (node (ref "JP3") (pin "8") (pinfunction "8_8") (pintype "passive"))
    )
    (net (code "76") (name "unconnected-(JP3-Pad10)") (class "Default")
      (node (ref "JP3") (pin "10") (pinfunction "10_10") (pintype "passive"))
    )
    (net (code "77") (name "unconnected-(JP3-Pad11)") (class "Default")
      (node (ref "JP3") (pin "11") (pinfunction "11_11") (pintype "passive"))
    )
    (net (code "78") (name "unconnected-(JP3-Pad12)") (class "Default")
      (node (ref "JP3") (pin "12") (pinfunction "12_12") (pintype "passive"))
    )
    (net (code "79") (name "unconnected-(JP3-Pad13)") (class "Default")
      (node (ref "JP3") (pin "13") (pinfunction "13_13") (pintype "passive"))
    )
    (net (code "80") (name "unconnected-(JP3-Pad15)") (class "Default")
      (node (ref "JP3") (pin "15") (pinfunction "15_15") (pintype "passive"))
    )
    (net (code "81") (name "unconnected-(JP3-Pad16)") (class "Default")
      (node (ref "JP3") (pin "16") (pinfunction "16_16") (pintype "passive"))
    )
    (net (code "82") (name "unconnected-(JP3-Pad17)") (class "Default")
      (node (ref "JP3") (pin "17") (pinfunction "17_17") (pintype "passive"))
    )
    (net (code "83") (name "unconnected-(JP3-Pad18)") (class "Default")
      (node (ref "JP3") (pin "18") (pinfunction "18_18") (pintype "passive"))
    )
    (net (code "84") (name "unconnected-(JP3-Pad19)") (class "Default")
      (node (ref "JP3") (pin "19") (pinfunction "19_19") (pintype "passive"))
    )
    (net (code "85") (name "unconnected-(JP3-Pad21)") (class "Default")
      (node (ref "JP3") (pin "21") (pinfunction "21_21") (pintype "passive"))
    )
    (net (code "86") (name "unconnected-(JP3-Pad22)") (class "Default")
      (node (ref "JP3") (pin "22") (pinfunction "22_22") (pintype "passive"))
    )
    (net (code "87") (name "unconnected-(JP3-Pad23)") (class "Default")
      (node (ref "JP3") (pin "23") (pinfunction "23_23") (pintype "passive"))
    )
    (net (code "88") (name "unconnected-(JP3-Pad24)") (class "Default")
      (node (ref "JP3") (pin "24") (pinfunction "24_24") (pintype "passive"))
    )
    (net (code "89") (name "unconnected-(JP3-Pad26)") (class "Default")
      (node (ref "JP3") (pin "26") (pinfunction "26_26") (pintype "passive"))
    )
    (net (code "90") (name "unconnected-(JP3-Pad27)") (class "Default")
      (node (ref "JP3") (pin "27") (pinfunction "27_27") (pintype "passive"))
    )
    (net (code "91") (name "unconnected-(JP3-Pad28)") (class "Default")
      (node (ref "JP3") (pin "28") (pinfunction "28_28") (pintype "passive"))
    )
    (net (code "92") (name "unconnected-(JP3-Pad29)") (class "Default")
      (node (ref "JP3") (pin "29") (pinfunction "29_29") (pintype "passive"))
    )
    (net (code "93") (name "unconnected-(JP3-Pad31)") (class "Default")
      (node (ref "JP3") (pin "31") (pinfunction "31_31") (pintype "passive"))
    )
    (net (code "94") (name "unconnected-(JP3-Pad32)") (class "Default")
      (node (ref "JP3") (pin "32") (pinfunction "32_32") (pintype "passive"))
    )
    (net (code "95") (name "unconnected-(JP3-Pad33)") (class "Default")
      (node (ref "JP3") (pin "33") (pinfunction "33_33") (pintype "passive"))
    )
    (net (code "96") (name "unconnected-(JP3-Pad35)") (class "Default")
      (node (ref "JP3") (pin "35") (pinfunction "35_35") (pintype "passive"))
    )
    (net (code "97") (name "unconnected-(JP3-Pad36)") (class "Default")
      (node (ref "JP3") (pin "36") (pinfunction "36_36") (pintype "passive"))
    )
    (net (code "98") (name "unconnected-(JP3-Pad37)") (class "Default")
      (node (ref "JP3") (pin "37") (pinfunction "37_37") (pintype "passive"))
    )
    (net (code "99") (name "unconnected-(JP3-Pad38)") (class "Default")
      (node (ref "JP3") (pin "38") (pinfunction "38_38") (pintype "passive"))
    )
    (net (code "100") (name "unconnected-(JP3-Pad40)") (class "Default")
      (node (ref "JP3") (pin "40") (pinfunction "40_40") (pintype "passive"))
    )
  )
)
